# monroe-hi.net
KiCad netlist of a schematic drawn in EAGLE
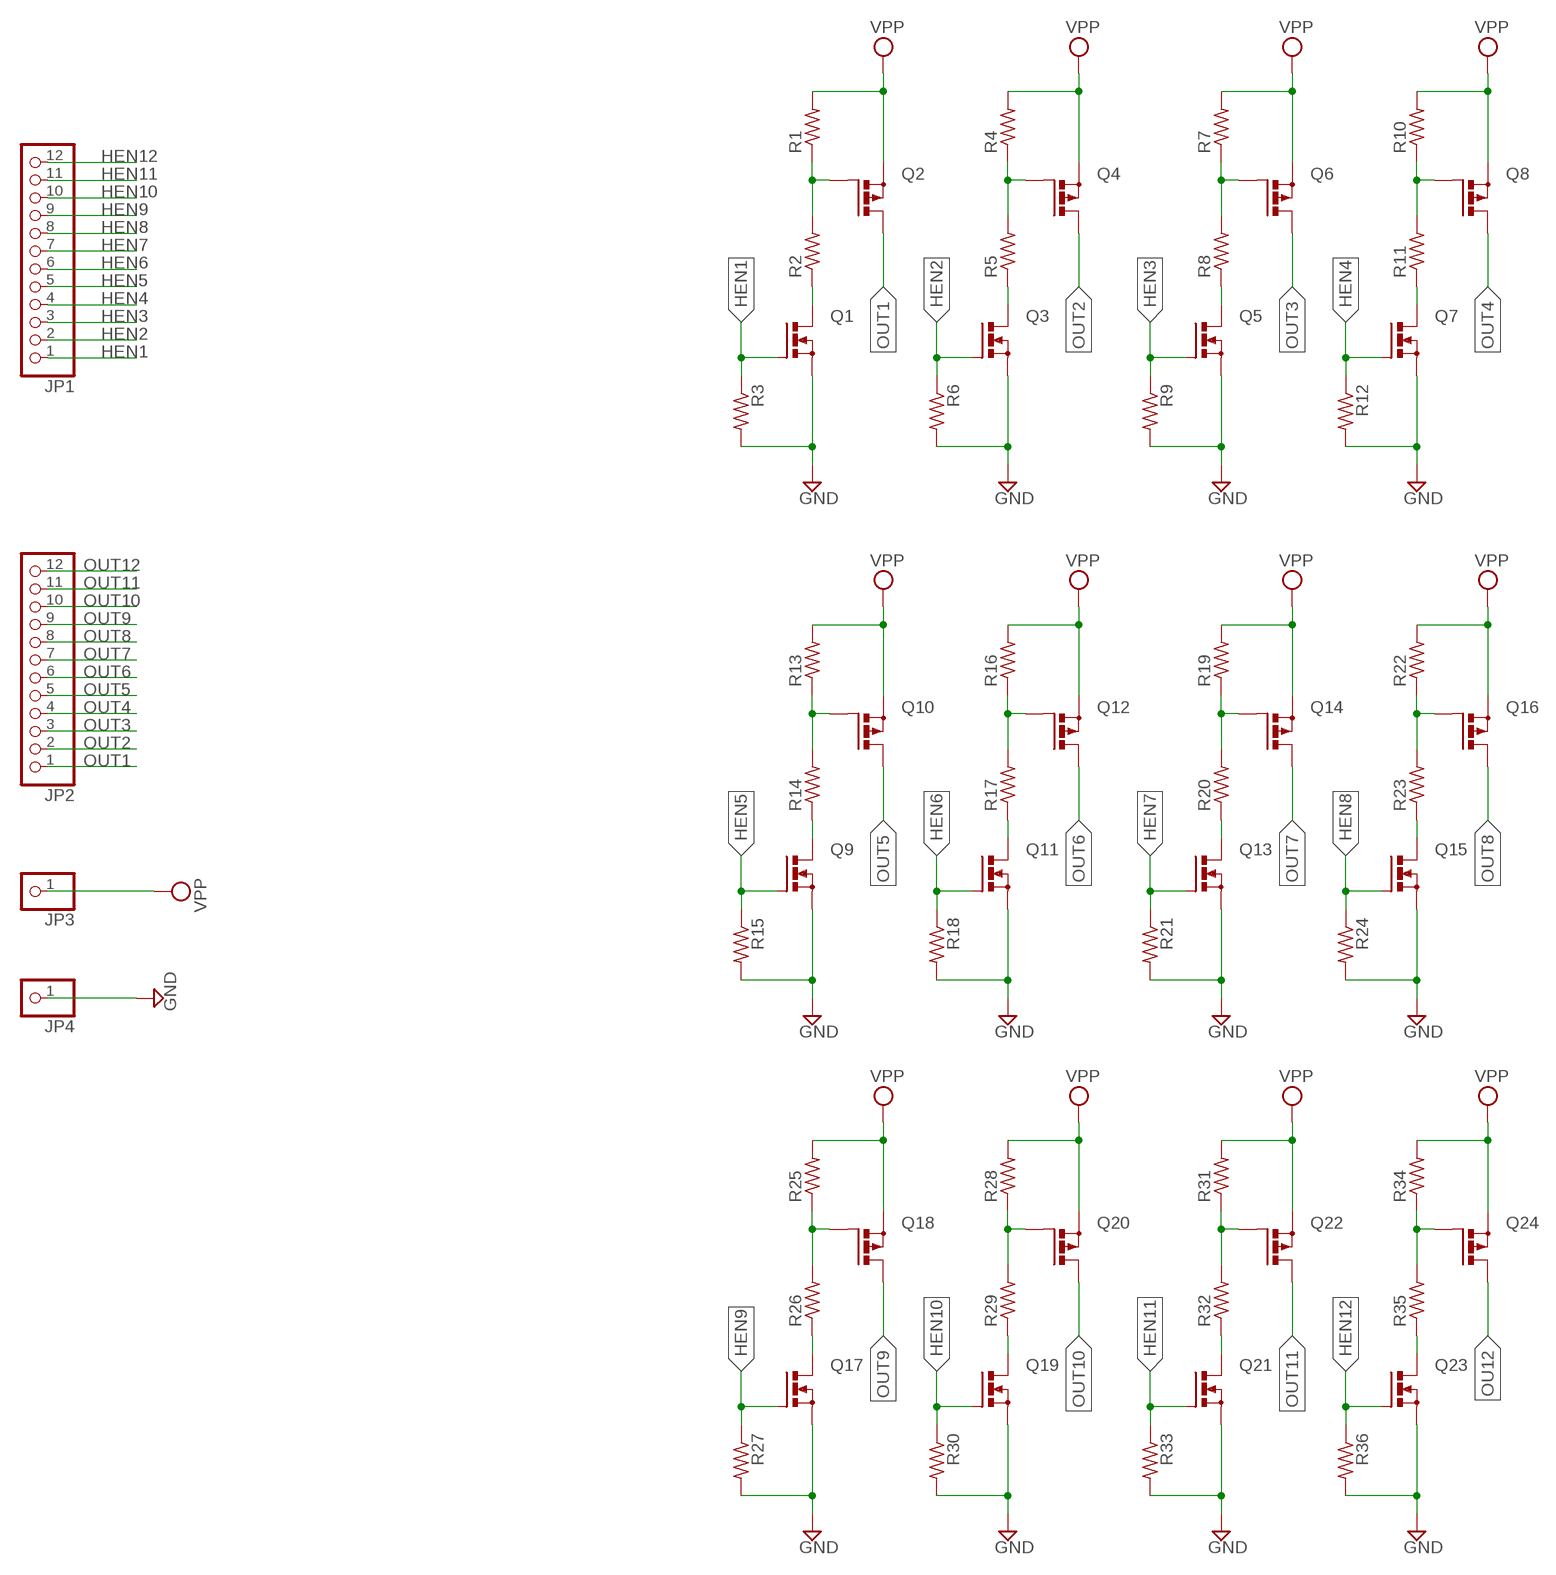
[diagram p0: schematic, sheet 1]

(export (version "E")
  (design (tool "Eeschema 10.0.6"))
  (components
    (comp (ref "JP1")
      (value "PINHD-1X12")
      (footprint "eagle-import:1X12")
      (libsource (lib "eagle-import") (part "PINHD-1X12"))
    )
    (comp (ref "JP2")
      (value "PINHD-1X12")
      (footprint "eagle-import:1X12")
      (libsource (lib "eagle-import") (part "PINHD-1X12"))
    )
    (comp (ref "JP3")
      (value "PINHD-1X1")
      (footprint "eagle-import:1X01")
      (libsource (lib "eagle-import") (part "PINHD-1X1"))
    )
    (comp (ref "JP4")
      (value "PINHD-1X1")
      (footprint "eagle-import:1X01")
      (libsource (lib "eagle-import") (part "PINHD-1X1"))
    )
    (comp (ref "Q1")
      (value "PMOSFET_NTO220BV")
      (footprint "eagle-import:TO220BV")
      (libsource (lib "eagle-import") (part "PMOSFET_NTO220BV"))
    )
    (comp (ref "Q2")
      (value "PMOSFET_PTO220BV")
      (footprint "eagle-import:TO220BV")
      (libsource (lib "eagle-import") (part "PMOSFET_PTO220BV"))
    )
    (comp (ref "Q3")
      (value "PMOSFET_NTO220BV")
      (footprint "eagle-import:TO220BV")
      (libsource (lib "eagle-import") (part "PMOSFET_NTO220BV"))
    )
    (comp (ref "Q4")
      (value "PMOSFET_PTO220BV")
      (footprint "eagle-import:TO220BV")
      (libsource (lib "eagle-import") (part "PMOSFET_PTO220BV"))
    )
    (comp (ref "Q5")
      (value "PMOSFET_NTO220BV")
      (footprint "eagle-import:TO220BV")
      (libsource (lib "eagle-import") (part "PMOSFET_NTO220BV"))
    )
    (comp (ref "Q6")
      (value "PMOSFET_PTO220BV")
      (footprint "eagle-import:TO220BV")
      (libsource (lib "eagle-import") (part "PMOSFET_PTO220BV"))
    )
    (comp (ref "Q7")
      (value "PMOSFET_NTO220BV")
      (footprint "eagle-import:TO220BV")
      (libsource (lib "eagle-import") (part "PMOSFET_NTO220BV"))
    )
    (comp (ref "Q8")
      (value "PMOSFET_PTO220BV")
      (footprint "eagle-import:TO220BV")
      (libsource (lib "eagle-import") (part "PMOSFET_PTO220BV"))
    )
    (comp (ref "Q9")
      (value "PMOSFET_NTO220BV")
      (footprint "eagle-import:TO220BV")
      (libsource (lib "eagle-import") (part "PMOSFET_NTO220BV"))
    )
    (comp (ref "Q10")
      (value "PMOSFET_PTO220BV")
      (footprint "eagle-import:TO220BV")
      (libsource (lib "eagle-import") (part "PMOSFET_PTO220BV"))
    )
    (comp (ref "Q11")
      (value "PMOSFET_NTO220BV")
      (footprint "eagle-import:TO220BV")
      (libsource (lib "eagle-import") (part "PMOSFET_NTO220BV"))
    )
    (comp (ref "Q12")
      (value "PMOSFET_PTO220BV")
      (footprint "eagle-import:TO220BV")
      (libsource (lib "eagle-import") (part "PMOSFET_PTO220BV"))
    )
    (comp (ref "Q13")
      (value "PMOSFET_NTO220BV")
      (footprint "eagle-import:TO220BV")
      (libsource (lib "eagle-import") (part "PMOSFET_NTO220BV"))
    )
    (comp (ref "Q14")
      (value "PMOSFET_PTO220BV")
      (footprint "eagle-import:TO220BV")
      (libsource (lib "eagle-import") (part "PMOSFET_PTO220BV"))
    )
    (comp (ref "Q15")
      (value "PMOSFET_NTO220BV")
      (footprint "eagle-import:TO220BV")
      (libsource (lib "eagle-import") (part "PMOSFET_NTO220BV"))
    )
    (comp (ref "Q16")
      (value "PMOSFET_PTO220BV")
      (footprint "eagle-import:TO220BV")
      (libsource (lib "eagle-import") (part "PMOSFET_PTO220BV"))
    )
    (comp (ref "Q17")
      (value "PMOSFET_NTO220BV")
      (footprint "eagle-import:TO220BV")
      (libsource (lib "eagle-import") (part "PMOSFET_NTO220BV"))
    )
    (comp (ref "Q18")
      (value "PMOSFET_PTO220BV")
      (footprint "eagle-import:TO220BV")
      (libsource (lib "eagle-import") (part "PMOSFET_PTO220BV"))
    )
    (comp (ref "Q19")
      (value "PMOSFET_NTO220BV")
      (footprint "eagle-import:TO220BV")
      (libsource (lib "eagle-import") (part "PMOSFET_NTO220BV"))
    )
    (comp (ref "Q20")
      (value "PMOSFET_PTO220BV")
      (footprint "eagle-import:TO220BV")
      (libsource (lib "eagle-import") (part "PMOSFET_PTO220BV"))
    )
    (comp (ref "Q21")
      (value "PMOSFET_NTO220BV")
      (footprint "eagle-import:TO220BV")
      (libsource (lib "eagle-import") (part "PMOSFET_NTO220BV"))
    )
    (comp (ref "Q22")
      (value "PMOSFET_PTO220BV")
      (footprint "eagle-import:TO220BV")
      (libsource (lib "eagle-import") (part "PMOSFET_PTO220BV"))
    )
    (comp (ref "Q23")
      (value "PMOSFET_NTO220BV")
      (footprint "eagle-import:TO220BV")
      (libsource (lib "eagle-import") (part "PMOSFET_NTO220BV"))
    )
    (comp (ref "Q24")
      (value "PMOSFET_PTO220BV")
      (footprint "eagle-import:TO220BV")
      (libsource (lib "eagle-import") (part "PMOSFET_PTO220BV"))
    )
    (comp (ref "R1")
      (value "R-US_0207/5V")
      (footprint "eagle-import:0207_5V")
      (libsource (lib "eagle-import") (part "R-US_0207/5V"))
    )
    (comp (ref "R2")
      (value "R-US_0207/5V")
      (footprint "eagle-import:0207_5V")
      (libsource (lib "eagle-import") (part "R-US_0207/5V"))
    )
    (comp (ref "R3")
      (value "R-US_0207/5V")
      (footprint "eagle-import:0207_5V")
      (libsource (lib "eagle-import") (part "R-US_0207/5V"))
    )
    (comp (ref "R4")
      (value "R-US_0207/5V")
      (footprint "eagle-import:0207_5V")
      (libsource (lib "eagle-import") (part "R-US_0207/5V"))
    )
    (comp (ref "R5")
      (value "R-US_0207/5V")
      (footprint "eagle-import:0207_5V")
      (libsource (lib "eagle-import") (part "R-US_0207/5V"))
    )
    (comp (ref "R6")
      (value "R-US_0207/5V")
      (footprint "eagle-import:0207_5V")
      (libsource (lib "eagle-import") (part "R-US_0207/5V"))
    )
    (comp (ref "R7")
      (value "R-US_0207/5V")
      (footprint "eagle-import:0207_5V")
      (libsource (lib "eagle-import") (part "R-US_0207/5V"))
    )
    (comp (ref "R8")
      (value "R-US_0207/5V")
      (footprint "eagle-import:0207_5V")
      (libsource (lib "eagle-import") (part "R-US_0207/5V"))
    )
    (comp (ref "R9")
      (value "R-US_0207/5V")
      (footprint "eagle-import:0207_5V")
      (libsource (lib "eagle-import") (part "R-US_0207/5V"))
    )
    (comp (ref "R10")
      (value "R-US_0207/5V")
      (footprint "eagle-import:0207_5V")
      (libsource (lib "eagle-import") (part "R-US_0207/5V"))
    )
    (comp (ref "R11")
      (value "R-US_0207/5V")
      (footprint "eagle-import:0207_5V")
      (libsource (lib "eagle-import") (part "R-US_0207/5V"))
    )
    (comp (ref "R12")
      (value "R-US_0207/5V")
      (footprint "eagle-import:0207_5V")
      (libsource (lib "eagle-import") (part "R-US_0207/5V"))
    )
    (comp (ref "R13")
      (value "R-US_0207/5V")
      (footprint "eagle-import:0207_5V")
      (libsource (lib "eagle-import") (part "R-US_0207/5V"))
    )
    (comp (ref "R14")
      (value "R-US_0207/5V")
      (footprint "eagle-import:0207_5V")
      (libsource (lib "eagle-import") (part "R-US_0207/5V"))
    )
    (comp (ref "R15")
      (value "R-US_0207/5V")
      (footprint "eagle-import:0207_5V")
      (libsource (lib "eagle-import") (part "R-US_0207/5V"))
    )
    (comp (ref "R16")
      (value "R-US_0207/5V")
      (footprint "eagle-import:0207_5V")
      (libsource (lib "eagle-import") (part "R-US_0207/5V"))
    )
    (comp (ref "R17")
      (value "R-US_0207/5V")
      (footprint "eagle-import:0207_5V")
      (libsource (lib "eagle-import") (part "R-US_0207/5V"))
    )
    (comp (ref "R18")
      (value "R-US_0207/5V")
      (footprint "eagle-import:0207_5V")
      (libsource (lib "eagle-import") (part "R-US_0207/5V"))
    )
    (comp (ref "R19")
      (value "R-US_0207/5V")
      (footprint "eagle-import:0207_5V")
      (libsource (lib "eagle-import") (part "R-US_0207/5V"))
    )
    (comp (ref "R20")
      (value "R-US_0207/5V")
      (footprint "eagle-import:0207_5V")
      (libsource (lib "eagle-import") (part "R-US_0207/5V"))
    )
    (comp (ref "R21")
      (value "R-US_0207/5V")
      (footprint "eagle-import:0207_5V")
      (libsource (lib "eagle-import") (part "R-US_0207/5V"))
    )
    (comp (ref "R22")
      (value "R-US_0207/5V")
      (footprint "eagle-import:0207_5V")
      (libsource (lib "eagle-import") (part "R-US_0207/5V"))
    )
    (comp (ref "R23")
      (value "R-US_0207/5V")
      (footprint "eagle-import:0207_5V")
      (libsource (lib "eagle-import") (part "R-US_0207/5V"))
    )
    (comp (ref "R24")
      (value "R-US_0207/5V")
      (footprint "eagle-import:0207_5V")
      (libsource (lib "eagle-import") (part "R-US_0207/5V"))
    )
    (comp (ref "R25")
      (value "R-US_0207/5V")
      (footprint "eagle-import:0207_5V")
      (libsource (lib "eagle-import") (part "R-US_0207/5V"))
    )
    (comp (ref "R26")
      (value "R-US_0207/5V")
      (footprint "eagle-import:0207_5V")
      (libsource (lib "eagle-import") (part "R-US_0207/5V"))
    )
    (comp (ref "R27")
      (value "R-US_0207/5V")
      (footprint "eagle-import:0207_5V")
      (libsource (lib "eagle-import") (part "R-US_0207/5V"))
    )
    (comp (ref "R28")
      (value "R-US_0207/5V")
      (footprint "eagle-import:0207_5V")
      (libsource (lib "eagle-import") (part "R-US_0207/5V"))
    )
    (comp (ref "R29")
      (value "R-US_0207/5V")
      (footprint "eagle-import:0207_5V")
      (libsource (lib "eagle-import") (part "R-US_0207/5V"))
    )
    (comp (ref "R30")
      (value "R-US_0207/5V")
      (footprint "eagle-import:0207_5V")
      (libsource (lib "eagle-import") (part "R-US_0207/5V"))
    )
    (comp (ref "R31")
      (value "R-US_0207/5V")
      (footprint "eagle-import:0207_5V")
      (libsource (lib "eagle-import") (part "R-US_0207/5V"))
    )
    (comp (ref "R32")
      (value "R-US_0207/5V")
      (footprint "eagle-import:0207_5V")
      (libsource (lib "eagle-import") (part "R-US_0207/5V"))
    )
    (comp (ref "R33")
      (value "R-US_0207/5V")
      (footprint "eagle-import:0207_5V")
      (libsource (lib "eagle-import") (part "R-US_0207/5V"))
    )
    (comp (ref "R34")
      (value "R-US_0207/5V")
      (footprint "eagle-import:0207_5V")
      (libsource (lib "eagle-import") (part "R-US_0207/5V"))
    )
    (comp (ref "R35")
      (value "R-US_0207/5V")
      (footprint "eagle-import:0207_5V")
      (libsource (lib "eagle-import") (part "R-US_0207/5V"))
    )
    (comp (ref "R36")
      (value "R-US_0207/5V")
      (footprint "eagle-import:0207_5V")
      (libsource (lib "eagle-import") (part "R-US_0207/5V"))
    )
  )
  (nets
    (net (code "1") (name "/OUT12") (class "Default")
      (node (ref "JP2") (pin "12") (pinfunction "12_12") (pintype "passive"))
    )
    (net (code "2") (name "GND") (class "Default")
      (node (ref "JP4") (pin "1") (pinfunction "1_1") (pintype "passive"))
      (node (ref "Q1") (pin "S") (pinfunction "S_S") (pintype "passive"))
      (node (ref "Q11") (pin "S") (pinfunction "S_S") (pintype "passive"))
      (node (ref "Q13") (pin "S") (pinfunction "S_S") (pintype "passive"))
      (node (ref "Q15") (pin "S") (pinfunction "S_S") (pintype "passive"))
      (node (ref "Q17") (pin "S") (pinfunction "S_S") (pintype "passive"))
      (node (ref "Q19") (pin "S") (pinfunction "S_S") (pintype "passive"))
      (node (ref "Q21") (pin "S") (pinfunction "S_S") (pintype "passive"))
      (node (ref "Q23") (pin "S") (pinfunction "S_S") (pintype "passive"))
      (node (ref "Q3") (pin "S") (pinfunction "S_S") (pintype "passive"))
      (node (ref "Q5") (pin "S") (pinfunction "S_S") (pintype "passive"))
      (node (ref "Q7") (pin "S") (pinfunction "S_S") (pintype "passive"))
      (node (ref "Q9") (pin "S") (pinfunction "S_S") (pintype "passive"))
      (node (ref "R12") (pin "2") (pinfunction "2_2") (pintype "passive"))
      (node (ref "R15") (pin "2") (pinfunction "2_2") (pintype "passive"))
      (node (ref "R18") (pin "2") (pinfunction "2_2") (pintype "passive"))
      (node (ref "R21") (pin "2") (pinfunction "2_2") (pintype "passive"))
      (node (ref "R24") (pin "2") (pinfunction "2_2") (pintype "passive"))
      (node (ref "R27") (pin "2") (pinfunction "2_2") (pintype "passive"))
      (node (ref "R3") (pin "2") (pinfunction "2_2") (pintype "passive"))
      (node (ref "R30") (pin "2") (pinfunction "2_2") (pintype "passive"))
      (node (ref "R33") (pin "2") (pinfunction "2_2") (pintype "passive"))
      (node (ref "R36") (pin "2") (pinfunction "2_2") (pintype "passive"))
      (node (ref "R6") (pin "2") (pinfunction "2_2") (pintype "passive"))
      (node (ref "R9") (pin "2") (pinfunction "2_2") (pintype "passive"))
    )
    (net (code "3") (name "HEN1") (class "Default")
      (node (ref "JP1") (pin "1") (pinfunction "1_1") (pintype "passive"))
      (node (ref "Q1") (pin "G") (pinfunction "G_G") (pintype "passive"))
      (node (ref "R3") (pin "1") (pinfunction "1_1") (pintype "passive"))
    )
    (net (code "4") (name "HEN2") (class "Default")
      (node (ref "JP1") (pin "2") (pinfunction "2_2") (pintype "passive"))
      (node (ref "Q3") (pin "G") (pinfunction "G_G") (pintype "passive"))
      (node (ref "R6") (pin "1") (pinfunction "1_1") (pintype "passive"))
    )
    (net (code "5") (name "HEN3") (class "Default")
      (node (ref "JP1") (pin "3") (pinfunction "3_3") (pintype "passive"))
      (node (ref "Q5") (pin "G") (pinfunction "G_G") (pintype "passive"))
      (node (ref "R9") (pin "1") (pinfunction "1_1") (pintype "passive"))
    )
    (net (code "6") (name "HEN4") (class "Default")
      (node (ref "JP1") (pin "4") (pinfunction "4_4") (pintype "passive"))
      (node (ref "Q7") (pin "G") (pinfunction "G_G") (pintype "passive"))
      (node (ref "R12") (pin "1") (pinfunction "1_1") (pintype "passive"))
    )
    (net (code "7") (name "HEN5") (class "Default")
      (node (ref "JP1") (pin "5") (pinfunction "5_5") (pintype "passive"))
      (node (ref "Q9") (pin "G") (pinfunction "G_G") (pintype "passive"))
      (node (ref "R15") (pin "1") (pinfunction "1_1") (pintype "passive"))
    )
    (net (code "8") (name "HEN6") (class "Default")
      (node (ref "JP1") (pin "6") (pinfunction "6_6") (pintype "passive"))
      (node (ref "Q11") (pin "G") (pinfunction "G_G") (pintype "passive"))
      (node (ref "R18") (pin "1") (pinfunction "1_1") (pintype "passive"))
    )
    (net (code "9") (name "HEN7") (class "Default")
      (node (ref "JP1") (pin "7") (pinfunction "7_7") (pintype "passive"))
      (node (ref "Q13") (pin "G") (pinfunction "G_G") (pintype "passive"))
      (node (ref "R21") (pin "1") (pinfunction "1_1") (pintype "passive"))
    )
    (net (code "10") (name "HEN8") (class "Default")
      (node (ref "JP1") (pin "8") (pinfunction "8_8") (pintype "passive"))
      (node (ref "Q15") (pin "G") (pinfunction "G_G") (pintype "passive"))
      (node (ref "R24") (pin "1") (pinfunction "1_1") (pintype "passive"))
    )
    (net (code "11") (name "HEN9") (class "Default")
      (node (ref "JP1") (pin "9") (pinfunction "9_9") (pintype "passive"))
      (node (ref "Q17") (pin "G") (pinfunction "G_G") (pintype "passive"))
      (node (ref "R27") (pin "1") (pinfunction "1_1") (pintype "passive"))
    )
    (net (code "12") (name "HEN10") (class "Default")
      (node (ref "JP1") (pin "10") (pinfunction "10_10") (pintype "passive"))
      (node (ref "Q19") (pin "G") (pinfunction "G_G") (pintype "passive"))
      (node (ref "R30") (pin "1") (pinfunction "1_1") (pintype "passive"))
    )
    (net (code "13") (name "HEN11") (class "Default")
      (node (ref "JP1") (pin "11") (pinfunction "11_11") (pintype "passive"))
      (node (ref "Q21") (pin "G") (pinfunction "G_G") (pintype "passive"))
      (node (ref "R33") (pin "1") (pinfunction "1_1") (pintype "passive"))
    )
    (net (code "14") (name "HEN12") (class "Default")
      (node (ref "JP1") (pin "12") (pinfunction "12_12") (pintype "passive"))
      (node (ref "Q23") (pin "G") (pinfunction "G_G") (pintype "passive"))
      (node (ref "R36") (pin "1") (pinfunction "1_1") (pintype "passive"))
    )
    (net (code "15") (name "Net-(Q1-PadD)") (class "Default")
      (node (ref "Q1") (pin "D") (pinfunction "D_D") (pintype "passive"))
      (node (ref "R2") (pin "1") (pinfunction "1_1") (pintype "passive"))
    )
    (net (code "16") (name "Net-(Q2-PadG)") (class "Default")
      (node (ref "Q2") (pin "G") (pinfunction "G_G") (pintype "passive"))
      (node (ref "R1") (pin "1") (pinfunction "1_1") (pintype "passive"))
      (node (ref "R2") (pin "2") (pinfunction "2_2") (pintype "passive"))
    )
    (net (code "17") (name "Net-(Q3-PadD)") (class "Default")
      (node (ref "Q3") (pin "D") (pinfunction "D_D") (pintype "passive"))
      (node (ref "R5") (pin "1") (pinfunction "1_1") (pintype "passive"))
    )
    (net (code "18") (name "Net-(Q4-PadG)") (class "Default")
      (node (ref "Q4") (pin "G") (pinfunction "G_G") (pintype "passive"))
      (node (ref "R4") (pin "1") (pinfunction "1_1") (pintype "passive"))
      (node (ref "R5") (pin "2") (pinfunction "2_2") (pintype "passive"))
    )
    (net (code "19") (name "Net-(Q5-PadD)") (class "Default")
      (node (ref "Q5") (pin "D") (pinfunction "D_D") (pintype "passive"))
      (node (ref "R8") (pin "1") (pinfunction "1_1") (pintype "passive"))
    )
    (net (code "20") (name "Net-(Q6-PadG)") (class "Default")
      (node (ref "Q6") (pin "G") (pinfunction "G_G") (pintype "passive"))
      (node (ref "R7") (pin "1") (pinfunction "1_1") (pintype "passive"))
      (node (ref "R8") (pin "2") (pinfunction "2_2") (pintype "passive"))
    )
    (net (code "21") (name "Net-(Q7-PadD)") (class "Default")
      (node (ref "Q7") (pin "D") (pinfunction "D_D") (pintype "passive"))
      (node (ref "R11") (pin "1") (pinfunction "1_1") (pintype "passive"))
    )
    (net (code "22") (name "Net-(Q8-PadG)") (class "Default")
      (node (ref "Q8") (pin "G") (pinfunction "G_G") (pintype "passive"))
      (node (ref "R10") (pin "1") (pinfunction "1_1") (pintype "passive"))
      (node (ref "R11") (pin "2") (pinfunction "2_2") (pintype "passive"))
    )
    (net (code "23") (name "Net-(Q9-PadD)") (class "Default")
      (node (ref "Q9") (pin "D") (pinfunction "D_D") (pintype "passive"))
      (node (ref "R14") (pin "1") (pinfunction "1_1") (pintype "passive"))
    )
    (net (code "24") (name "Net-(Q10-PadG)") (class "Default")
      (node (ref "Q10") (pin "G") (pinfunction "G_G") (pintype "passive"))
      (node (ref "R13") (pin "1") (pinfunction "1_1") (pintype "passive"))
      (node (ref "R14") (pin "2") (pinfunction "2_2") (pintype "passive"))
    )
    (net (code "25") (name "Net-(Q11-PadD)") (class "Default")
      (node (ref "Q11") (pin "D") (pinfunction "D_D") (pintype "passive"))
      (node (ref "R17") (pin "1") (pinfunction "1_1") (pintype "passive"))
    )
    (net (code "26") (name "Net-(Q12-PadG)") (class "Default")
      (node (ref "Q12") (pin "G") (pinfunction "G_G") (pintype "passive"))
      (node (ref "R16") (pin "1") (pinfunction "1_1") (pintype "passive"))
      (node (ref "R17") (pin "2") (pinfunction "2_2") (pintype "passive"))
    )
    (net (code "27") (name "Net-(Q13-PadD)") (class "Default")
      (node (ref "Q13") (pin "D") (pinfunction "D_D") (pintype "passive"))
      (node (ref "R20") (pin "1") (pinfunction "1_1") (pintype "passive"))
    )
    (net (code "28") (name "Net-(Q14-PadG)") (class "Default")
      (node (ref "Q14") (pin "G") (pinfunction "G_G") (pintype "passive"))
      (node (ref "R19") (pin "1") (pinfunction "1_1") (pintype "passive"))
      (node (ref "R20") (pin "2") (pinfunction "2_2") (pintype "passive"))
    )
    (net (code "29") (name "Net-(Q15-PadD)") (class "Default")
      (node (ref "Q15") (pin "D") (pinfunction "D_D") (pintype "passive"))
      (node (ref "R23") (pin "1") (pinfunction "1_1") (pintype "passive"))
    )
    (net (code "30") (name "Net-(Q16-PadG)") (class "Default")
      (node (ref "Q16") (pin "G") (pinfunction "G_G") (pintype "passive"))
      (node (ref "R22") (pin "1") (pinfunction "1_1") (pintype "passive"))
      (node (ref "R23") (pin "2") (pinfunction "2_2") (pintype "passive"))
    )
    (net (code "31") (name "Net-(Q17-PadD)") (class "Default")
      (node (ref "Q17") (pin "D") (pinfunction "D_D") (pintype "passive"))
      (node (ref "R26") (pin "1") (pinfunction "1_1") (pintype "passive"))
    )
    (net (code "32") (name "Net-(Q18-PadG)") (class "Default")
      (node (ref "Q18") (pin "G") (pinfunction "G_G") (pintype "passive"))
      (node (ref "R25") (pin "1") (pinfunction "1_1") (pintype "passive"))
      (node (ref "R26") (pin "2") (pinfunction "2_2") (pintype "passive"))
    )
    (net (code "33") (name "Net-(Q19-PadD)") (class "Default")
      (node (ref "Q19") (pin "D") (pinfunction "D_D") (pintype "passive"))
      (node (ref "R29") (pin "1") (pinfunction "1_1") (pintype "passive"))
    )
    (net (code "34") (name "Net-(Q20-PadG)") (class "Default")
      (node (ref "Q20") (pin "G") (pinfunction "G_G") (pintype "passive"))
      (node (ref "R28") (pin "1") (pinfunction "1_1") (pintype "passive"))
      (node (ref "R29") (pin "2") (pinfunction "2_2") (pintype "passive"))
    )
    (net (code "35") (name "Net-(Q21-PadD)") (class "Default")
      (node (ref "Q21") (pin "D") (pinfunction "D_D") (pintype "passive"))
      (node (ref "R32") (pin "1") (pinfunction "1_1") (pintype "passive"))
    )
    (net (code "36") (name "Net-(Q22-PadG)") (class "Default")
      (node (ref "Q22") (pin "G") (pinfunction "G_G") (pintype "passive"))
      (node (ref "R31") (pin "1") (pinfunction "1_1") (pintype "passive"))
      (node (ref "R32") (pin "2") (pinfunction "2_2") (pintype "passive"))
    )
    (net (code "37") (name "Net-(Q23-PadD)") (class "Default")
      (node (ref "Q23") (pin "D") (pinfunction "D_D") (pintype "passive"))
      (node (ref "R35") (pin "1") (pinfunction "1_1") (pintype "passive"))
    )
    (net (code "38") (name "Net-(Q24-PadG)") (class "Default")
      (node (ref "Q24") (pin "G") (pinfunction "G_G") (pintype "passive"))
      (node (ref "R34") (pin "1") (pinfunction "1_1") (pintype "passive"))
      (node (ref "R35") (pin "2") (pinfunction "2_2") (pintype "passive"))
    )
    (net (code "39") (name "OU12") (class "Default")
      (node (ref "Q24") (pin "D") (pinfunction "D_D") (pintype "passive"))
    )
    (net (code "40") (name "OUT1") (class "Default")
      (node (ref "JP2") (pin "1") (pinfunction "1_1") (pintype "passive"))
      (node (ref "Q2") (pin "D") (pinfunction "D_D") (pintype "passive"))
    )
    (net (code "41") (name "OUT2") (class "Default")
      (node (ref "JP2") (pin "2") (pinfunction "2_2") (pintype "passive"))
      (node (ref "Q4") (pin "D") (pinfunction "D_D") (pintype "passive"))
    )
    (net (code "42") (name "OUT3") (class "Default")
      (node (ref "JP2") (pin "3") (pinfunction "3_3") (pintype "passive"))
      (node (ref "Q6") (pin "D") (pinfunction "D_D") (pintype "passive"))
    )
    (net (code "43") (name "OUT4") (class "Default")
      (node (ref "JP2") (pin "4") (pinfunction "4_4") (pintype "passive"))
      (node (ref "Q8") (pin "D") (pinfunction "D_D") (pintype "passive"))
    )
    (net (code "44") (name "OUT5") (class "Default")
      (node (ref "JP2") (pin "5") (pinfunction "5_5") (pintype "passive"))
      (node (ref "Q10") (pin "D") (pinfunction "D_D") (pintype "passive"))
    )
    (net (code "45") (name "OUT6") (class "Default")
      (node (ref "JP2") (pin "6") (pinfunction "6_6") (pintype "passive"))
      (node (ref "Q12") (pin "D") (pinfunction "D_D") (pintype "passive"))
    )
    (net (code "46") (name "OUT7") (class "Default")
      (node (ref "JP2") (pin "7") (pinfunction "7_7") (pintype "passive"))
      (node (ref "Q14") (pin "D") (pinfunction "D_D") (pintype "passive"))
    )
    (net (code "47") (name "OUT8") (class "Default")
      (node (ref "JP2") (pin "8") (pinfunction "8_8") (pintype "passive"))
      (node (ref "Q16") (pin "D") (pinfunction "D_D") (pintype "passive"))
    )
    (net (code "48") (name "OUT9") (class "Default")
      (node (ref "JP2") (pin "9") (pinfunction "9_9") (pintype "passive"))
      (node (ref "Q18") (pin "D") (pinfunction "D_D") (pintype "passive"))
    )
    (net (code "49") (name "OUT10") (class "Default")
      (node (ref "JP2") (pin "10") (pinfunction "10_10") (pintype "passive"))
      (node (ref "Q20") (pin "D") (pinfunction "D_D") (pintype "passive"))
    )
    (net (code "50") (name "OUT11") (class "Default")
      (node (ref "JP2") (pin "11") (pinfunction "11_11") (pintype "passive"))
      (node (ref "Q22") (pin "D") (pinfunction "D_D") (pintype "passive"))
    )
    (net (code "51") (name "VPP") (class "Default")
      (node (ref "JP3") (pin "1") (pinfunction "1_1") (pintype "passive"))
      (node (ref "Q10") (pin "S") (pinfunction "S_S") (pintype "passive"))
      (node (ref "Q12") (pin "S") (pinfunction "S_S") (pintype "passive"))
      (node (ref "Q14") (pin "S") (pinfunction "S_S") (pintype "passive"))
      (node (ref "Q16") (pin "S") (pinfunction "S_S") (pintype "passive"))
      (node (ref "Q18") (pin "S") (pinfunction "S_S") (pintype "passive"))
      (node (ref "Q2") (pin "S") (pinfunction "S_S") (pintype "passive"))
      (node (ref "Q20") (pin "S") (pinfunction "S_S") (pintype "passive"))
      (node (ref "Q22") (pin "S") (pinfunction "S_S") (pintype "passive"))
      (node (ref "Q24") (pin "S") (pinfunction "S_S") (pintype "passive"))
      (node (ref "Q4") (pin "S") (pinfunction "S_S") (pintype "passive"))
      (node (ref "Q6") (pin "S") (pinfunction "S_S") (pintype "passive"))
      (node (ref "Q8") (pin "S") (pinfunction "S_S") (pintype "passive"))
      (node (ref "R1") (pin "2") (pinfunction "2_2") (pintype "passive"))
      (node (ref "R10") (pin "2") (pinfunction "2_2") (pintype "passive"))
      (node (ref "R13") (pin "2") (pinfunction "2_2") (pintype "passive"))
      (node (ref "R16") (pin "2") (pinfunction "2_2") (pintype "passive"))
      (node (ref "R19") (pin "2") (pinfunction "2_2") (pintype "passive"))
      (node (ref "R22") (pin "2") (pinfunction "2_2") (pintype "passive"))
      (node (ref "R25") (pin "2") (pinfunction "2_2") (pintype "passive"))
      (node (ref "R28") (pin "2") (pinfunction "2_2") (pintype "passive"))
      (node (ref "R31") (pin "2") (pinfunction "2_2") (pintype "passive"))
      (node (ref "R34") (pin "2") (pinfunction "2_2") (pintype "passive"))
      (node (ref "R4") (pin "2") (pinfunction "2_2") (pintype "passive"))
      (node (ref "R7") (pin "2") (pinfunction "2_2") (pintype "passive"))
    )
  )
)
